# LM2596.net
KiCad netlist of a schematic drawn in Altium Designer
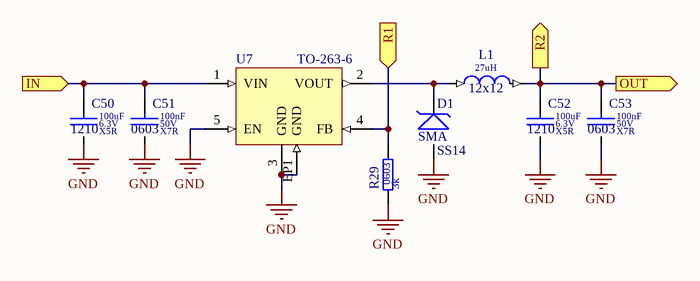
[diagram p0: LM2596.SchDoc]

(export (version "E")
  (design (tool "Eeschema 10.0.6"))
  (components
    (comp (ref "C50")
      (value "100uF")
      (footprint "C_1210_3225")
      (description "Capacitor")
      (fields
        (field (name "DIELECTRIC") "X5R")
        (field (name "VOLTAGE") "6.3V")
        (field (name "SCH_FOOTPRINT") "1210")
        (field (name "PART NUMBER") "C_100uF_6.3V_X5R_1210_20")
        (field (name "MANUFACTURER") "TDK")
      )
      (libsource (lib "Library") (part "C"))
    )
    (comp (ref "C51")
      (value "100nF")
      (footprint "C_0603_1608")
      (description "Capacitor")
      (fields
        (field (name "DIELECTRIC") "X7R")
        (field (name "VOLTAGE") "50V")
        (field (name "SCH_FOOTPRINT") "0603")
        (field (name "PART NUMBER") "C_100nF_50V_X7R_0603_5")
        (field (name "MANUFACTURER") "Samsung")
      )
      (libsource (lib "Library") (part "C"))
    )
    (comp (ref "C52")
      (value "100uF")
      (footprint "C_1210_3225")
      (description "Capacitor")
      (fields
        (field (name "DIELECTRIC") "X5R")
        (field (name "VOLTAGE") "6.3V")
        (field (name "SCH_FOOTPRINT") "1210")
        (field (name "PART NUMBER") "C_100uF_6.3V_X5R_1210_20")
        (field (name "MANUFACTURER") "TDK")
      )
      (libsource (lib "Library") (part "C"))
    )
    (comp (ref "C53")
      (value "100nF")
      (footprint "C_0603_1608")
      (description "Capacitor")
      (fields
        (field (name "DIELECTRIC") "X7R")
        (field (name "VOLTAGE") "50V")
        (field (name "SCH_FOOTPRINT") "0603")
        (field (name "PART NUMBER") "C_100nF_50V_X7R_0603_5")
        (field (name "MANUFACTURER") "Samsung")
      )
      (libsource (lib "Library") (part "C"))
    )
    (comp (ref "D1")
      (value "SS14")
      (footprint "SMA_DO-214AC")
      (fields
        (field (name "SCH_FOOTPRINT") "SMA")
        (field (name "PART NUMBER") "DS_SS14_1A_40V_SMA")
        (field (name "VOLTAGE") "40V")
        (field (name "MANUFACTURER") "Fairchild Semiconductor")
      )
      (libsource (lib "Library") (part "DS"))
    )
    (comp (ref "L1")
      (value "27uH")
      (footprint "L_SRR1280-XXXY")
      (description "Induction")
      (fields
        (field (name "SCH_FOOTPRINT") "12x12")
        (field (name "PART NUMBER") "L_27uH_3.9A_SRR1280")
        (field (name "MANUFACTURER") "Bourns")
      )
      (libsource (lib "Library") (part "L"))
    )
    (comp (ref "R29")
      (value "3k")
      (footprint "R_NC_0603_1608")
      (fields
        (field (name "SCH_FOOTPRINT") "0603")
        (field (name "PART NUMBER") "R_GENERIC_0603")
        (field (name "Comment") "Resistor")
      )
      (libsource (lib "Library") (part "R"))
    )
    (comp (ref "U7")
      (value "VR_LM2596")
      (footprint "TO-263-6")
      (fields (field (name "SCH_FOOTPRINT") "TO-263-6") (field (name "PART NUMBER") "VR_LM2596-ADJ"))
      (libsource (lib "Lib") (part "VR_LM2596"))
    )
  )
  (nets
    (net (code "1") (name "/IN") (class "Default")
      (node (ref "C50") (pin "1") (pinfunction "1_1") (pintype "passive"))
      (node (ref "C51") (pin "1") (pinfunction "1_1") (pintype "passive"))
      (node (ref "U7") (pin "1") (pinfunction "VIN_1") (pintype "input"))
    )
    (net (code "2") (name "/OUT") (class "Default")
      (node (ref "C52") (pin "1") (pinfunction "1_1") (pintype "passive"))
      (node (ref "C53") (pin "1") (pinfunction "1_1") (pintype "passive"))
      (node (ref "L1") (pin "2") (pinfunction "2_2") (pintype "output"))
    )
    (net (code "3") (name "/R1") (class "Default")
      (node (ref "R29") (pin "2") (pinfunction "2_2") (pintype "passive"))
      (node (ref "U7") (pin "4") (pinfunction "FB_4") (pintype "input"))
    )
    (net (code "4") (name "GND") (class "Default")
      (node (ref "C50") (pin "2") (pinfunction "2_2") (pintype "passive"))
      (node (ref "C51") (pin "2") (pinfunction "2_2") (pintype "passive"))
      (node (ref "C52") (pin "2") (pinfunction "2_2") (pintype "passive"))
      (node (ref "C53") (pin "2") (pinfunction "2_2") (pintype "passive"))
      (node (ref "D1") (pin "2") (pintype "passive"))
      (node (ref "R29") (pin "1") (pinfunction "1_1") (pintype "passive"))
      (node (ref "U7") (pin "3") (pinfunction "GND_3") (pintype "power_in"))
      (node (ref "U7") (pin "5") (pinfunction "EN_5") (pintype "input"))
      (node (ref "U7") (pin "EP1") (pinfunction "GND_EP1") (pintype "input"))
    )
    (net (code "5") (name "Net-(U7-VOUT)") (class "Default")
      (node (ref "D1") (pin "1") (pintype "passive"))
      (node (ref "L1") (pin "1") (pinfunction "1_1") (pintype "input"))
      (node (ref "U7") (pin "2") (pinfunction "VOUT_2") (pintype "output"))
    )
  )
)
